# LEDProject.net
KiCad netlist of a schematic drawn in Altium Designer
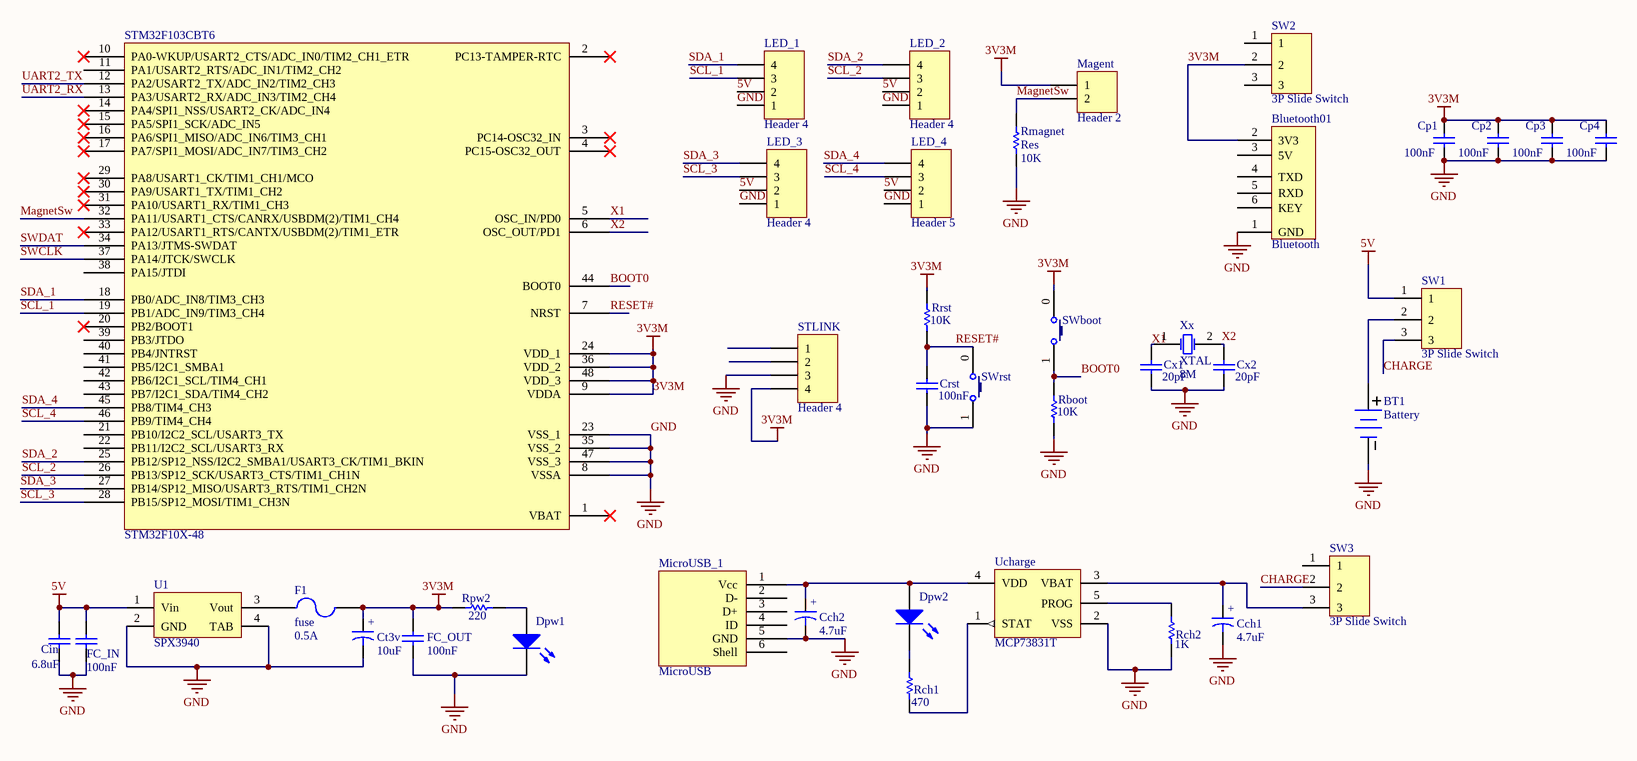
[diagram p0: LEDProject.SchDoc]

(export (version "E")
  (design (tool "Eeschema 10.0.6"))
  (components
    (comp (ref "Bluetooth01")
      (value "Bluetooth")
      (footprint "Bluetooth Module")
      (description "Bluetooth Module")
      (libsource (lib "u025Library") (part "Bluetooth Module"))
    )
    (comp (ref "BT1")
      (value "Battery")
      (footprint "BAT-2")
      (description "Multicell Battery")
      (fields (field (name "PUBLISHER") "Altium Limited"))
      (libsource (lib "u025Library") (part "Battery"))
    )
    (comp (ref "Cch1")
      (value "4.7uF")
      (footprint "Tantalum Cap Size A")
      (description "Electrolytic CAP")
      (fields (field (name "Comment") "CAP2"))
      (libsource (lib "u025Library") (part "CAP2"))
    )
    (comp (ref "Cch2")
      (value "4.7uF")
      (footprint "Tantalum Cap Size A")
      (description "Electrolytic CAP")
      (fields (field (name "Comment") "CAP2"))
      (libsource (lib "u025Library") (part "CAP2"))
    )
    (comp (ref "Cin")
      (value "6.8uF")
      (footprint "SMD-C-0805")
      (description "Capacitor_SMD")
      (fields (field (name "Comment") "CAP1"))
      (libsource (lib "u025Library") (part "CAP1"))
    )
    (comp (ref "Cp1")
      (value "100nF")
      (footprint "SMD-C-0805")
      (description "Capacitor_SMD")
      (fields (field (name "Comment") "CAP1"))
      (libsource (lib "u025Library") (part "CAP1"))
    )
    (comp (ref "Cp2")
      (value "100nF")
      (footprint "SMD-C-0805")
      (description "Capacitor_SMD")
      (fields (field (name "Comment") "CAP1"))
      (libsource (lib "u025Library") (part "CAP1"))
    )
    (comp (ref "Cp3")
      (value "100nF")
      (footprint "SMD-C-0805")
      (description "Capacitor_SMD")
      (fields (field (name "Comment") "CAP1"))
      (libsource (lib "u025Library") (part "CAP1"))
    )
    (comp (ref "Cp4")
      (value "100nF")
      (footprint "SMD-C-0805")
      (description "Capacitor_SMD")
      (fields (field (name "Comment") "CAP1"))
      (libsource (lib "u025Library") (part "CAP1"))
    )
    (comp (ref "Crst")
      (value "100nF")
      (footprint "SMD-C-0805")
      (description "Capacitor_SMD")
      (fields (field (name "Comment") "CAP1"))
      (libsource (lib "u025Library") (part "CAP1"))
    )
    (comp (ref "Ct3v")
      (value "10uF")
      (footprint "Tantalum Cap Size A")
      (description "Electrolytic CAP")
      (fields (field (name "Comment") "CAP2"))
      (libsource (lib "u025Library") (part "CAP2"))
    )
    (comp (ref "Cx1")
      (value "20pF")
      (footprint "SMD-C-0805")
      (description "Capacitor_SMD")
      (fields (field (name "Comment") "CAP1"))
      (libsource (lib "u025Library") (part "CAP1"))
    )
    (comp (ref "Cx2")
      (value "20pF")
      (footprint "SMD-C-0805")
      (description "Capacitor_SMD")
      (fields (field (name "Comment") "CAP1"))
      (libsource (lib "u025Library") (part "CAP1"))
    )
    (comp (ref "Dpw1")
      (value "SMD LED")
      (footprint "SMT LED 0603")
      (description "Typical RED GaAs LED")
      (fields (field (name "PUBLISHER") "Altium Limited"))
      (libsource (lib "u025Library") (part "SMD LED"))
    )
    (comp (ref "Dpw2")
      (value "SMD LED")
      (footprint "SMT LED 0603")
      (description "Typical RED GaAs LED")
      (fields (field (name "PUBLISHER") "Altium Limited"))
      (libsource (lib "u025Library") (part "SMD LED"))
    )
    (comp (ref "F1")
      (value "fuse")
      (footprint "FUSE_SMD")
      (fields (field (name "ALTIUM_VALUE") "0.5A"))
      (libsource (lib "u025Library") (part "fuse"))
    )
    (comp (ref "FC_IN")
      (value "100nF")
      (footprint "SMD-C-0805")
      (description "Capacitor_SMD")
      (fields (field (name "Comment") "CAP1"))
      (libsource (lib "u025Library") (part "CAP1"))
    )
    (comp (ref "FC_OUT")
      (value "100nF")
      (footprint "SMD-C-0805")
      (description "Capacitor_SMD")
      (fields (field (name "Comment") "CAP1"))
      (libsource (lib "u025Library") (part "CAP1"))
    )
    (comp (ref "LED_1")
      (value "Header 4")
      (footprint "HDR1X4")
      (description "Header, 4-Pin")
      (fields (field (name "PUBLISHER") "Altium Limited"))
      (libsource (lib "Miscellaneous Connectors") (part "Header 4"))
    )
    (comp (ref "LED_2")
      (value "Header 4")
      (footprint "HDR1X4")
      (description "Header, 4-Pin")
      (fields (field (name "PUBLISHER") "Altium Limited"))
      (libsource (lib "Miscellaneous Connectors") (part "Header 4"))
    )
    (comp (ref "LED_3")
      (value "Header 4")
      (footprint "HDR1X4")
      (description "Header, 4-Pin")
      (fields (field (name "PUBLISHER") "Altium Limited"))
      (libsource (lib "Miscellaneous Connectors") (part "Header 4"))
    )
    (comp (ref "LED_4")
      (value "Header 5")
      (footprint "HDR1X4")
      (description "Header, 4-Pin")
      (fields (field (name "PUBLISHER") "Altium Limited"))
      (libsource (lib "Miscellaneous Connectors") (part "Header 4"))
    )
    (comp (ref "Magent")
      (value "Header 2")
      (footprint "HDR1X2")
      (description "Header, 2-Pin")
      (fields (field (name "PUBLISHER") "Altium Limited"))
      (libsource (lib "Miscellaneous Connectors") (part "Header 2"))
    )
    (comp (ref "MicroUSB_1")
      (value "MicroUSB")
      (footprint "MicroUSB")
      (libsource (lib "u025Library") (part "MicroUSB"))
    )
    (comp (ref "Rboot")
      (value "10K")
      (footprint "SMD-R-0603")
      (description "Resistor")
      (fields (field (name "Comment") "Res") (field (name "PUBLISHER") "Altium Limited"))
      (libsource (lib "u025Library") (part "Res"))
    )
    (comp (ref "Rch1")
      (value "470")
      (footprint "SMD-R-0603")
      (description "Resistor")
      (fields (field (name "Comment") "Res") (field (name "PUBLISHER") "Altium Limited"))
      (libsource (lib "u025Library") (part "Res"))
    )
    (comp (ref "Rch2")
      (value "1K")
      (footprint "SMD-R-0603")
      (description "Resistor")
      (fields (field (name "Comment") "Res") (field (name "PUBLISHER") "Altium Limited"))
      (libsource (lib "u025Library") (part "Res"))
    )
    (comp (ref "Rmagnet")
      (value "Res")
      (footprint "SMD-R-0603")
      (description "Resistor")
      (fields (field (name "ALTIUM_VALUE") "10K") (field (name "PUBLISHER") "Altium Limited"))
      (libsource (lib "u025Library") (part "Res"))
    )
    (comp (ref "Rpw2")
      (value "220")
      (footprint "SMD-R-0603")
      (description "Resistor")
      (fields (field (name "Comment") "Res") (field (name "PUBLISHER") "Altium Limited"))
      (libsource (lib "u025Library") (part "Res"))
    )
    (comp (ref "Rrst")
      (value "10K")
      (footprint "SMD-R-0603")
      (description "Resistor")
      (fields (field (name "Comment") "Res") (field (name "PUBLISHER") "Altium Limited"))
      (libsource (lib "u025Library") (part "Res"))
    )
    (comp (ref "STLINK")
      (value "Header 4")
      (footprint "HDR1X4")
      (description "Header, 4-Pin")
      (fields (field (name "PUBLISHER") "Altium Limited"))
      (libsource (lib "") (part "Header 4_1"))
    )
    (comp (ref "STM32F103CBT6")
      (value "STM32F10X-48")
      (footprint "LQFP48_N")
      (description "STM32 ARM-based 32-bit MCU , 48-pin LQFP, Industrial Temperature")
      (fields (field (name "PUBLISHER") "Altium Limited"))
      (libsource (lib "u025Library") (part "STM32F10X-48"))
    )
    (comp (ref "SW1")
      (value "3P Slide Switch")
      (footprint "3P_Smooth_Switch_90")
      (description "3Pin Slide Switch")
      (libsource (lib "u025Library") (part "3P Slide Switch"))
    )
    (comp (ref "SW2")
      (value "3P Slide Switch")
      (footprint "3P_Smooth_Switch_90")
      (description "3Pin Slide Switch")
      (libsource (lib "u025Library") (part "3P Slide Switch"))
    )
    (comp (ref "SW3")
      (value "3P Slide Switch")
      (footprint "3P_Smooth_Switch_90")
      (description "3Pin Slide Switch")
      (libsource (lib "u025Library") (part "3P Slide Switch"))
    )
    (comp (ref "SWboot")
      (value "SWrst")
      (footprint "Button2_SMD")
      (description "Button2_SMD")
      (libsource (lib "u025Library") (part "Button2_SMD"))
    )
    (comp (ref "SWrst")
      (value "SWrst")
      (footprint "Button2_SMD")
      (description "Button2_SMD")
      (libsource (lib "u025Library") (part "Button2_SMD"))
    )
    (comp (ref "U1")
      (value "SPX3940")
      (footprint "SOT-223")
      (description "1A Low Dropout Voltage Regulator")
      (libsource (lib "u025Library") (part "SPX3940"))
    )
    (comp (ref "Ucharge")
      (value "MCP73831T")
      (footprint "SOT23-5_N")
      (fields (field (name "PUBLISHER") "Altium Limited"))
      (libsource (lib "u025Library") (part "MCP73831T"))
    )
    (comp (ref "Xx")
      (value "XTAL")
      (footprint "CRYSTAL-2x6")
      (fields (field (name "ALTIUM_VALUE") "8M"))
      (libsource (lib "u025Library") (part "XTAL"))
    )
  )
  (nets
    (net (code "1") (name "/BOOT0") (class "Default")
      (node (ref "Rboot") (pin "2") (pinfunction "2_2") (pintype "passive"))
      (node (ref "STM32F103CBT6") (pin "44") (pinfunction "BOOT0_44") (pintype "passive"))
      (node (ref "SWboot") (pin "1") (pinfunction "1_1") (pintype "passive"))
    )
    (net (code "2") (name "/CHARGE") (class "Default")
      (node (ref "SW1") (pin "3") (pinfunction "3_3") (pintype "passive"))
      (node (ref "SW3") (pin "2") (pinfunction "2_2") (pintype "passive"))
    )
    (net (code "3") (name "/MagnetSw") (class "Default")
      (node (ref "Magent") (pin "2") (pinfunction "2_2") (pintype "passive"))
      (node (ref "Rmagnet") (pin "2") (pinfunction "2_2") (pintype "passive"))
      (node (ref "STM32F103CBT6") (pin "32") (pinfunction "PA11/USART1_CTS/CANRX/USBDM(2)/TIM1_CH4_32") (pintype "passive"))
    )
    (net (code "4") (name "/RESET#") (class "Default")
      (node (ref "Crst") (pin "1") (pinfunction "1_1") (pintype "passive"))
      (node (ref "Rrst") (pin "1") (pinfunction "1_1") (pintype "passive"))
      (node (ref "STM32F103CBT6") (pin "7") (pinfunction "NRST_7") (pintype "passive"))
      (node (ref "SWrst") (pin "0") (pinfunction "0_0") (pintype "passive"))
    )
    (net (code "5") (name "/SCL_1") (class "Default")
      (node (ref "LED_1") (pin "3") (pinfunction "3_3") (pintype "passive"))
      (node (ref "STM32F103CBT6") (pin "19") (pinfunction "PB1/ADC_IN9/TIM3_CH4_19") (pintype "passive"))
    )
    (net (code "6") (name "/SCL_2") (class "Default")
      (node (ref "LED_2") (pin "3") (pinfunction "3_3") (pintype "passive"))
      (node (ref "STM32F103CBT6") (pin "26") (pinfunction "PB13/SP12_SCK/USART3_CTS/TIM1_CH1N_26") (pintype "passive"))
    )
    (net (code "7") (name "/SCL_3") (class "Default")
      (node (ref "LED_3") (pin "3") (pinfunction "3_3") (pintype "passive"))
      (node (ref "STM32F103CBT6") (pin "28") (pinfunction "PB15/SP12_MOSI/TIM1_CH3N_28") (pintype "passive"))
    )
    (net (code "8") (name "/SCL_4") (class "Default")
      (node (ref "LED_4") (pin "3") (pinfunction "3_3") (pintype "passive"))
      (node (ref "STM32F103CBT6") (pin "46") (pinfunction "PB9/TIM4_CH4_46") (pintype "passive"))
    )
    (net (code "9") (name "/SDA_1") (class "Default")
      (node (ref "LED_1") (pin "4") (pinfunction "4_4") (pintype "passive"))
      (node (ref "STM32F103CBT6") (pin "18") (pinfunction "PB0/ADC_IN8/TIM3_CH3_18") (pintype "passive"))
    )
    (net (code "10") (name "/SDA_2") (class "Default")
      (node (ref "LED_2") (pin "4") (pinfunction "4_4") (pintype "passive"))
      (node (ref "STM32F103CBT6") (pin "25") (pinfunction "PB12/SP12_NSS/I2C2_SMBA1/USART3_CK/TIM1_BKIN_25") (pintype "passive"))
    )
    (net (code "11") (name "/SDA_3") (class "Default")
      (node (ref "LED_3") (pin "4") (pinfunction "4_4") (pintype "passive"))
      (node (ref "STM32F103CBT6") (pin "27") (pinfunction "PB14/SP12_MISO/USART3_RTS/TIM1_CH2N_27") (pintype "passive"))
    )
    (net (code "12") (name "/SDA_4") (class "Default")
      (node (ref "LED_4") (pin "4") (pinfunction "4_4") (pintype "passive"))
      (node (ref "STM32F103CBT6") (pin "45") (pinfunction "PB8/TIM4_CH3_45") (pintype "passive"))
    )
    (net (code "13") (name "/SWCLK") (class "Default")
      (node (ref "STM32F103CBT6") (pin "37") (pinfunction "PA14/JTCK/SWCLK_37") (pintype "passive"))
    )
    (net (code "14") (name "/SWDAT") (class "Default")
      (node (ref "STM32F103CBT6") (pin "34") (pinfunction "PA13/JTMS-SWDAT_34") (pintype "passive"))
    )
    (net (code "15") (name "/UART2_RX") (class "Default")
      (node (ref "STM32F103CBT6") (pin "13") (pinfunction "PA3/USART2_RX/ADC_IN3/TIM2_CH4_13") (pintype "passive"))
    )
    (net (code "16") (name "/UART2_TX") (class "Default")
      (node (ref "STM32F103CBT6") (pin "12") (pinfunction "PA2/USART2_TX/ADC_IN2/TIM2_CH3_12") (pintype "passive"))
    )
    (net (code "17") (name "/X1") (class "Default")
      (node (ref "Cx1") (pin "1") (pinfunction "1_1") (pintype "passive"))
      (node (ref "STM32F103CBT6") (pin "5") (pinfunction "OSC_IN/PD0_5") (pintype "passive"))
      (node (ref "Xx") (pin "1") (pinfunction "OSC1_1") (pintype "passive"))
    )
    (net (code "18") (name "/X2") (class "Default")
      (node (ref "Cx2") (pin "1") (pinfunction "1_1") (pintype "passive"))
      (node (ref "STM32F103CBT6") (pin "6") (pinfunction "OSC_OUT/PD1_6") (pintype "passive"))
      (node (ref "Xx") (pin "2") (pinfunction "OSC2_2") (pintype "passive"))
    )
    (net (code "19") (name "3V3M") (class "Default")
      (node (ref "Bluetooth01") (pin "2") (pinfunction "3V3_2") (pintype "passive"))
      (node (ref "Cp1") (pin "2") (pinfunction "2_2") (pintype "passive"))
      (node (ref "Cp2") (pin "2") (pinfunction "2_2") (pintype "passive"))
      (node (ref "Cp3") (pin "2") (pinfunction "2_2") (pintype "passive"))
      (node (ref "Cp4") (pin "2") (pinfunction "2_2") (pintype "passive"))
      (node (ref "Ct3v") (pin "1") (pinfunction "1_1") (pintype "passive"))
      (node (ref "F1") (pin "2") (pinfunction "2_2") (pintype "passive"))
      (node (ref "FC_OUT") (pin "2") (pinfunction "2_2") (pintype "passive"))
      (node (ref "Magent") (pin "1") (pinfunction "1_1") (pintype "passive"))
      (node (ref "Rpw2") (pin "1") (pinfunction "1_1") (pintype "passive"))
      (node (ref "Rrst") (pin "2") (pinfunction "2_2") (pintype "passive"))
      (node (ref "STLINK") (pin "4") (pinfunction "4_4") (pintype "passive"))
      (node (ref "STM32F103CBT6") (pin "24") (pinfunction "VDD_1_24") (pintype "power_in"))
      (node (ref "STM32F103CBT6") (pin "36") (pinfunction "VDD_2_36") (pintype "power_in"))
      (node (ref "STM32F103CBT6") (pin "48") (pinfunction "VDD_3_48") (pintype "power_in"))
      (node (ref "STM32F103CBT6") (pin "9") (pinfunction "VDDA_9") (pintype "power_in"))
      (node (ref "SW2") (pin "2") (pinfunction "2_2") (pintype "passive"))
      (node (ref "SWboot") (pin "0") (pinfunction "0_0") (pintype "passive"))
    )
    (net (code "20") (name "5V") (class "Default")
      (node (ref "Cin") (pin "2") (pinfunction "2_2") (pintype "passive"))
      (node (ref "FC_IN") (pin "2") (pinfunction "2_2") (pintype "passive"))
      (node (ref "LED_1") (pin "2") (pinfunction "2_2") (pintype "passive"))
      (node (ref "LED_2") (pin "2") (pinfunction "2_2") (pintype "passive"))
      (node (ref "LED_3") (pin "2") (pinfunction "2_2") (pintype "passive"))
      (node (ref "LED_4") (pin "2") (pinfunction "2_2") (pintype "passive"))
      (node (ref "SW1") (pin "1") (pinfunction "1_1") (pintype "passive"))
      (node (ref "U1") (pin "1") (pinfunction "Vin_1") (pintype "passive"))
    )
    (net (code "21") (name "GND") (class "Default")
      (node (ref "BT1") (pin "2") (pinfunction "-_2") (pintype "passive"))
      (node (ref "Bluetooth01") (pin "1") (pinfunction "GND_1") (pintype "passive"))
      (node (ref "Cch1") (pin "2") (pinfunction "2_2") (pintype "passive"))
      (node (ref "Cch2") (pin "2") (pinfunction "2_2") (pintype "passive"))
      (node (ref "Cin") (pin "1") (pinfunction "1_1") (pintype "passive"))
      (node (ref "Cp1") (pin "1") (pinfunction "1_1") (pintype "passive"))
      (node (ref "Cp2") (pin "1") (pinfunction "1_1") (pintype "passive"))
      (node (ref "Cp3") (pin "1") (pinfunction "1_1") (pintype "passive"))
      (node (ref "Cp4") (pin "1") (pinfunction "1_1") (pintype "passive"))
      (node (ref "Crst") (pin "2") (pinfunction "2_2") (pintype "passive"))
      (node (ref "Ct3v") (pin "2") (pinfunction "2_2") (pintype "passive"))
      (node (ref "Cx1") (pin "2") (pinfunction "2_2") (pintype "passive"))
      (node (ref "Cx2") (pin "2") (pinfunction "2_2") (pintype "passive"))
      (node (ref "Dpw1") (pin "2") (pinfunction "K_2") (pintype "passive"))
      (node (ref "FC_IN") (pin "1") (pinfunction "1_1") (pintype "passive"))
      (node (ref "FC_OUT") (pin "1") (pinfunction "1_1") (pintype "passive"))
      (node (ref "LED_1") (pin "1") (pinfunction "1_1") (pintype "passive"))
      (node (ref "LED_2") (pin "1") (pinfunction "1_1") (pintype "passive"))
      (node (ref "LED_3") (pin "1") (pinfunction "1_1") (pintype "passive"))
      (node (ref "LED_4") (pin "1") (pinfunction "1_1") (pintype "passive"))
      (node (ref "MicroUSB_1") (pin "5") (pinfunction "GND_5") (pintype "passive"))
      (node (ref "Rboot") (pin "1") (pinfunction "1_1") (pintype "passive"))
      (node (ref "Rch2") (pin "1") (pinfunction "1_1") (pintype "passive"))
      (node (ref "Rmagnet") (pin "1") (pinfunction "1_1") (pintype "passive"))
      (node (ref "STLINK") (pin "3") (pinfunction "3_3") (pintype "passive"))
      (node (ref "STM32F103CBT6") (pin "23") (pinfunction "VSS_1_23") (pintype "power_in"))
      (node (ref "STM32F103CBT6") (pin "35") (pinfunction "VSS_2_35") (pintype "power_in"))
      (node (ref "STM32F103CBT6") (pin "47") (pinfunction "VSS_3_47") (pintype "power_in"))
      (node (ref "STM32F103CBT6") (pin "8") (pinfunction "VSSA_8") (pintype "power_in"))
      (node (ref "SWrst") (pin "1") (pinfunction "1_1") (pintype "passive"))
      (node (ref "U1") (pin "2") (pinfunction "GND_2") (pintype "passive"))
      (node (ref "U1") (pin "4") (pinfunction "TAB_4") (pintype "passive"))
      (node (ref "Ucharge") (pin "2") (pinfunction "VSS_2") (pintype "passive"))
    )
    (net (code "22") (name "Net-(BT1-+)") (class "Default")
      (node (ref "BT1") (pin "1") (pinfunction "+_1") (pintype "passive"))
      (node (ref "SW1") (pin "2") (pinfunction "2_2") (pintype "passive"))
    )
    (net (code "23") (name "Net-(Dpw1-A)") (class "Default")
      (node (ref "Dpw1") (pin "1") (pinfunction "A_1") (pintype "passive"))
      (node (ref "Rpw2") (pin "2") (pinfunction "2_2") (pintype "passive"))
    )
    (net (code "24") (name "Net-(Dpw2-A)") (class "Default")
      (node (ref "Cch2") (pin "1") (pinfunction "1_1") (pintype "passive"))
      (node (ref "Dpw2") (pin "1") (pinfunction "A_1") (pintype "passive"))
      (node (ref "MicroUSB_1") (pin "1") (pinfunction "Vcc_1") (pintype "passive"))
      (node (ref "Ucharge") (pin "4") (pinfunction "VDD_4") (pintype "passive"))
    )
    (net (code "25") (name "Net-(Dpw2-K)") (class "Default")
      (node (ref "Dpw2") (pin "2") (pinfunction "K_2") (pintype "passive"))
      (node (ref "Rch1") (pin "2") (pinfunction "2_2") (pintype "passive"))
    )
    (net (code "26") (name "Net-(U1-Vout)") (class "Default")
      (node (ref "F1") (pin "1") (pinfunction "1_1") (pintype "passive"))
      (node (ref "U1") (pin "3") (pinfunction "Vout_3") (pintype "passive"))
    )
    (net (code "27") (name "Net-(Ucharge-PROG)") (class "Default")
      (node (ref "Rch2") (pin "2") (pinfunction "2_2") (pintype "passive"))
      (node (ref "Ucharge") (pin "5") (pinfunction "PROG_5") (pintype "passive"))
    )
    (net (code "28") (name "Net-(Ucharge-STAT)") (class "Default")
      (node (ref "Rch1") (pin "1") (pinfunction "1_1") (pintype "passive"))
      (node (ref "Ucharge") (pin "1") (pinfunction "STAT_1") (pintype "output"))
    )
    (net (code "29") (name "Net-(Ucharge-VBAT)") (class "Default")
      (node (ref "Cch1") (pin "1") (pinfunction "1_1") (pintype "passive"))
      (node (ref "SW3") (pin "3") (pinfunction "3_3") (pintype "passive"))
      (node (ref "Ucharge") (pin "3") (pinfunction "VBAT_3") (pintype "passive"))
    )
    (net (code "30") (name "unconnected-(Bluetooth01-5V-Pad3)") (class "Default")
      (node (ref "Bluetooth01") (pin "3") (pinfunction "5V_3") (pintype "passive"))
    )
    (net (code "31") (name "unconnected-(Bluetooth01-KEY-Pad6)") (class "Default")
      (node (ref "Bluetooth01") (pin "6") (pinfunction "KEY_6") (pintype "passive"))
    )
    (net (code "32") (name "unconnected-(Bluetooth01-RXD-Pad5)") (class "Default")
      (node (ref "Bluetooth01") (pin "5") (pinfunction "RXD_5") (pintype "passive"))
    )
    (net (code "33") (name "unconnected-(Bluetooth01-TXD-Pad4)") (class "Default")
      (node (ref "Bluetooth01") (pin "4") (pinfunction "TXD_4") (pintype "passive"))
    )
    (net (code "34") (name "unconnected-(MicroUSB_1-D+-Pad3)") (class "Default")
      (node (ref "MicroUSB_1") (pin "3") (pinfunction "D+_3") (pintype "passive"))
    )
    (net (code "35") (name "unconnected-(MicroUSB_1-D--Pad2)") (class "Default")
      (node (ref "MicroUSB_1") (pin "2") (pinfunction "D-_2") (pintype "passive"))
    )
    (net (code "36") (name "unconnected-(MicroUSB_1-ID-Pad4)") (class "Default")
      (node (ref "MicroUSB_1") (pin "4") (pinfunction "ID_4") (pintype "passive"))
    )
    (net (code "37") (name "unconnected-(MicroUSB_1-Shell-Pad6)") (class "Default")
      (node (ref "MicroUSB_1") (pin "6") (pinfunction "Shell_6") (pintype "passive"))
    )
    (net (code "38") (name "unconnected-(STLINK-Pad1)") (class "Default")
      (node (ref "STLINK") (pin "1") (pinfunction "1_1") (pintype "passive"))
    )
    (net (code "39") (name "unconnected-(STLINK-Pad2)") (class "Default")
      (node (ref "STLINK") (pin "2") (pinfunction "2_2") (pintype "passive"))
    )
    (net (code "40") (name "unconnected-(STM32F103CBT6-PA0-WKUP{slash}USART2_CTS{slash}ADC_IN0{slash}TIM2_CH1_ETR-Pad10)") (class "Default")
      (node (ref "STM32F103CBT6") (pin "10") (pinfunction "PA0-WKUP/USART2_CTS/ADC_IN0/TIM2_CH1_ETR_10") (pintype "passive+no_connect"))
    )
    (net (code "41") (name "unconnected-(STM32F103CBT6-PA1{slash}USART2_RTS{slash}ADC_IN1{slash}TIM2_CH2-Pad11)") (class "Default")
      (node (ref "STM32F103CBT6") (pin "11") (pinfunction "PA1/USART2_RTS/ADC_IN1/TIM2_CH2_11") (pintype "passive"))
    )
    (net (code "42") (name "unconnected-(STM32F103CBT6-PA4{slash}SPI1_NSS{slash}USART2_CK{slash}ADC_IN4-Pad14)") (class "Default")
      (node (ref "STM32F103CBT6") (pin "14") (pinfunction "PA4/SPI1_NSS/USART2_CK/ADC_IN4_14") (pintype "passive+no_connect"))
    )
    (net (code "43") (name "unconnected-(STM32F103CBT6-PA5{slash}SPI1_SCK{slash}ADC_IN5-Pad15)") (class "Default")
      (node (ref "STM32F103CBT6") (pin "15") (pinfunction "PA5/SPI1_SCK/ADC_IN5_15") (pintype "passive+no_connect"))
    )
    (net (code "44") (name "unconnected-(STM32F103CBT6-PA6{slash}SPI1_MISO{slash}ADC_IN6{slash}TIM3_CH1-Pad16)") (class "Default")
      (node (ref "STM32F103CBT6") (pin "16") (pinfunction "PA6/SPI1_MISO/ADC_IN6/TIM3_CH1_16") (pintype "passive+no_connect"))
    )
    (net (code "45") (name "unconnected-(STM32F103CBT6-PA7{slash}SPI1_MOSI{slash}ADC_IN7{slash}TIM3_CH2-Pad17)") (class "Default")
      (node (ref "STM32F103CBT6") (pin "17") (pinfunction "PA7/SPI1_MOSI/ADC_IN7/TIM3_CH2_17") (pintype "passive+no_connect"))
    )
    (net (code "46") (name "unconnected-(STM32F103CBT6-PA8{slash}USART1_CK{slash}TIM1_CH1{slash}MCO-Pad29)") (class "Default")
      (node (ref "STM32F103CBT6") (pin "29") (pinfunction "PA8/USART1_CK/TIM1_CH1/MCO_29") (pintype "passive+no_connect"))
    )
    (net (code "47") (name "unconnected-(STM32F103CBT6-PA9{slash}USART1_TX{slash}TIM1_CH2-Pad30)") (class "Default")
      (node (ref "STM32F103CBT6") (pin "30") (pinfunction "PA9/USART1_TX/TIM1_CH2_30") (pintype "passive+no_connect"))
    )
    (net (code "48") (name "unconnected-(STM32F103CBT6-PA10{slash}USART1_RX{slash}TIM1_CH3-Pad31)") (class "Default")
      (node (ref "STM32F103CBT6") (pin "31") (pinfunction "PA10/USART1_RX/TIM1_CH3_31") (pintype "passive+no_connect"))
    )
    (net (code "49") (name "unconnected-(STM32F103CBT6-PA12{slash}USART1_RTS{slash}CANTX{slash}USBDM(2){slash}TIM1_ETR-Pad33)") (class "Default")
      (node (ref "STM32F103CBT6") (pin "33") (pinfunction "PA12/USART1_RTS/CANTX/USBDM(2)/TIM1_ETR_33") (pintype "passive+no_connect"))
    )
    (net (code "50") (name "unconnected-(STM32F103CBT6-PA15{slash}JTDI-Pad38)") (class "Default")
      (node (ref "STM32F103CBT6") (pin "38") (pinfunction "PA15/JTDI_38") (pintype "passive"))
    )
    (net (code "51") (name "unconnected-(STM32F103CBT6-PB2{slash}BOOT1-Pad20)") (class "Default")
      (node (ref "STM32F103CBT6") (pin "20") (pinfunction "PB2/BOOT1_20") (pintype "passive+no_connect"))
    )
    (net (code "52") (name "unconnected-(STM32F103CBT6-PB3{slash}JTDO-Pad39)") (class "Default")
      (node (ref "STM32F103CBT6") (pin "39") (pinfunction "PB3/JTDO_39") (pintype "passive"))
    )
    (net (code "53") (name "unconnected-(STM32F103CBT6-PB4{slash}JNTRST-Pad40)") (class "Default")
      (node (ref "STM32F103CBT6") (pin "40") (pinfunction "PB4/JNTRST_40") (pintype "passive"))
    )
    (net (code "54") (name "unconnected-(STM32F103CBT6-PB5{slash}I2C1_SMBA1-Pad41)") (class "Default")
      (node (ref "STM32F103CBT6") (pin "41") (pinfunction "PB5/I2C1_SMBA1_41") (pintype "passive"))
    )
    (net (code "55") (name "unconnected-(STM32F103CBT6-PB6{slash}I2C1_SCL{slash}TIM4_CH1-Pad42)") (class "Default")
      (node (ref "STM32F103CBT6") (pin "42") (pinfunction "PB6/I2C1_SCL/TIM4_CH1_42") (pintype "passive"))
    )
    (net (code "56") (name "unconnected-(STM32F103CBT6-PB7{slash}I2C1_SDA{slash}TIM4_CH2-Pad43)") (class "Default")
      (node (ref "STM32F103CBT6") (pin "43") (pinfunction "PB7/I2C1_SDA/TIM4_CH2_43") (pintype "passive"))
    )
    (net (code "57") (name "unconnected-(STM32F103CBT6-PB10{slash}I2C2_SCL{slash}USART3_TX-Pad21)") (class "Default")
      (node (ref "STM32F103CBT6") (pin "21") (pinfunction "PB10/I2C2_SCL/USART3_TX_21") (pintype "passive"))
    )
    (net (code "58") (name "unconnected-(STM32F103CBT6-PB11{slash}I2C2_SCL{slash}USART3_RX-Pad22)") (class "Default")
      (node (ref "STM32F103CBT6") (pin "22") (pinfunction "PB11/I2C2_SCL/USART3_RX_22") (pintype "passive"))
    )
    (net (code "59") (name "unconnected-(STM32F103CBT6-PC13-TAMPER-RTC-Pad2)") (class "Default")
      (node (ref "STM32F103CBT6") (pin "2") (pinfunction "PC13-TAMPER-RTC_2") (pintype "passive+no_connect"))
    )
    (net (code "60") (name "unconnected-(STM32F103CBT6-PC14-OSC32_IN-Pad3)") (class "Default")
      (node (ref "STM32F103CBT6") (pin "3") (pinfunction "PC14-OSC32_IN_3") (pintype "passive+no_connect"))
    )
    (net (code "61") (name "unconnected-(STM32F103CBT6-PC15-OSC32_OUT-Pad4)") (class "Default")
      (node (ref "STM32F103CBT6") (pin "4") (pinfunction "PC15-OSC32_OUT_4") (pintype "passive+no_connect"))
    )
    (net (code "62") (name "unconnected-(STM32F103CBT6-VBAT-Pad1)") (class "Default")
      (node (ref "STM32F103CBT6") (pin "1") (pinfunction "VBAT_1") (pintype "power_in+no_connect"))
    )
    (net (code "63") (name "unconnected-(SW2-Pad1)") (class "Default")
      (node (ref "SW2") (pin "1") (pinfunction "1_1") (pintype "passive"))
    )
    (net (code "64") (name "unconnected-(SW2-Pad3)") (class "Default")
      (node (ref "SW2") (pin "3") (pinfunction "3_3") (pintype "passive"))
    )
    (net (code "65") (name "unconnected-(SW3-Pad1)") (class "Default")
      (node (ref "SW3") (pin "1") (pinfunction "1_1") (pintype "passive"))
    )
  )
)
